# HVBoard.net
KiCad netlist of a schematic drawn in EAGLE
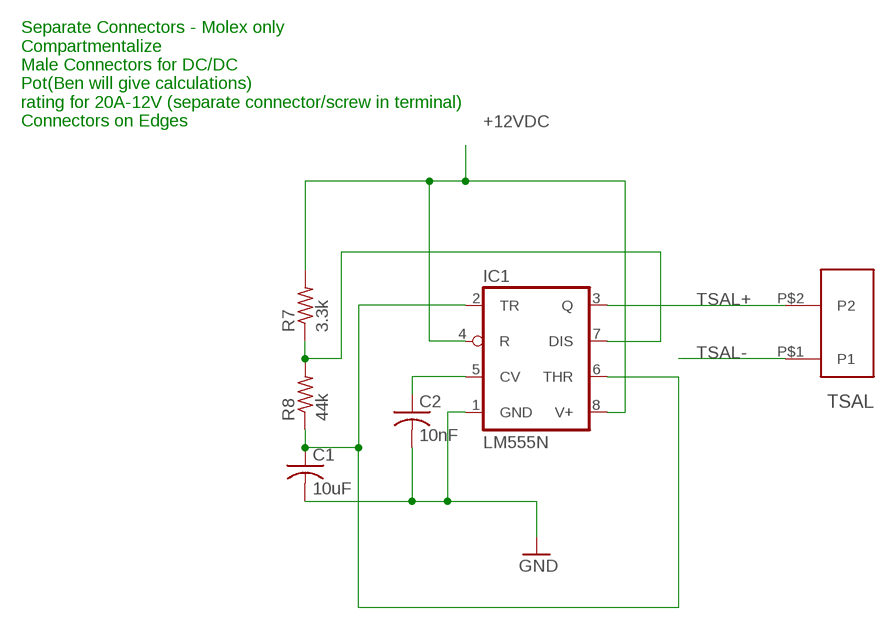
[diagram p0: schematic, sheet 1]
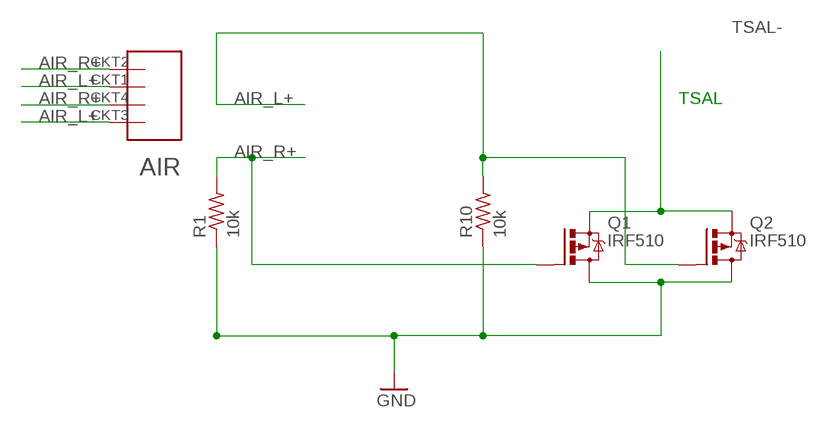
[diagram p1: schematic, sheet 2]
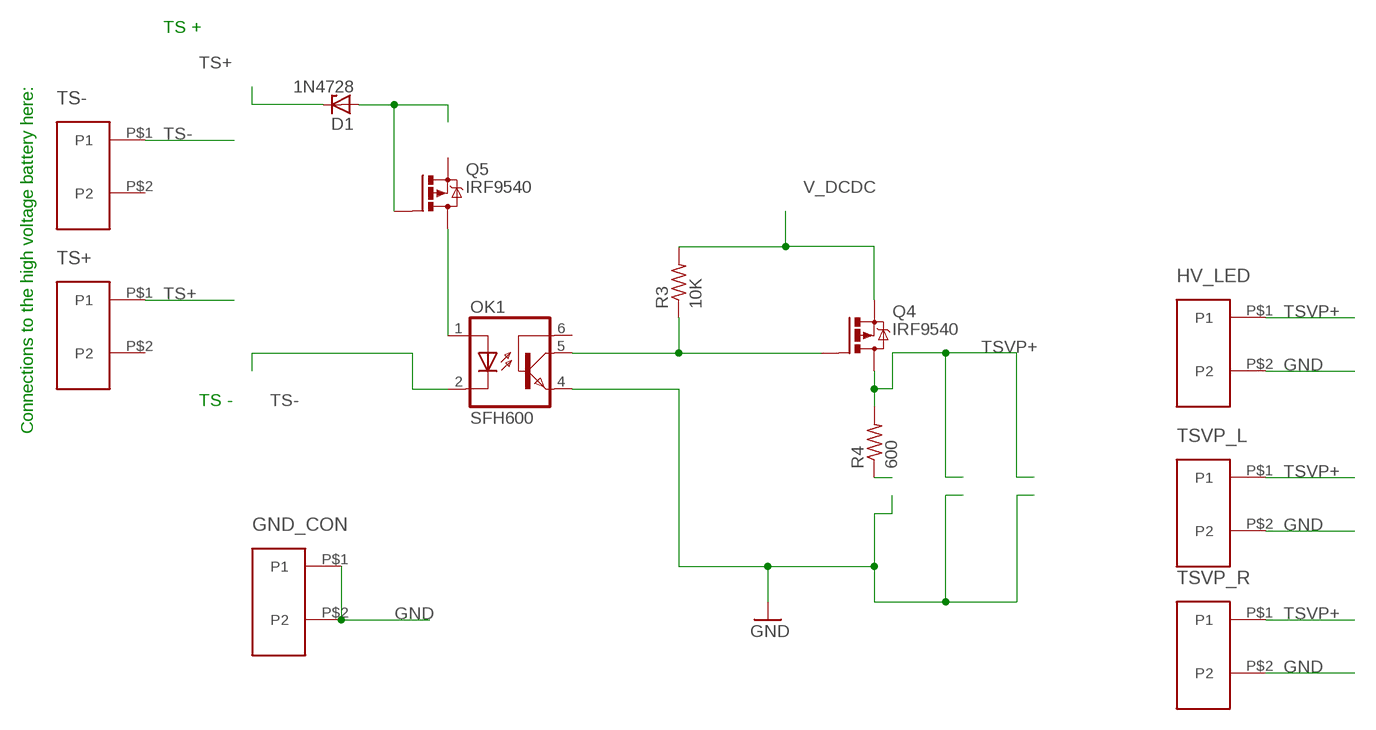
[diagram p2: schematic, sheet 3]
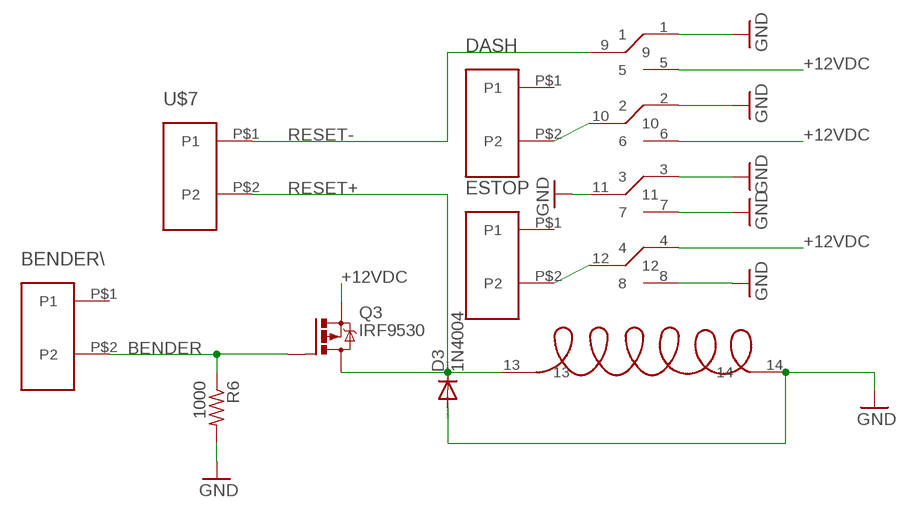
[diagram p3: schematic, sheet 4]
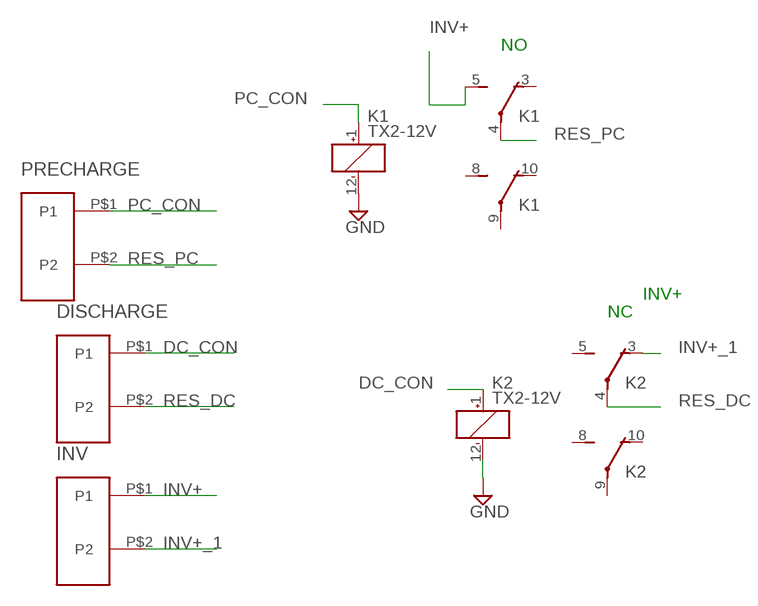
[diagram p4: schematic, sheet 5]
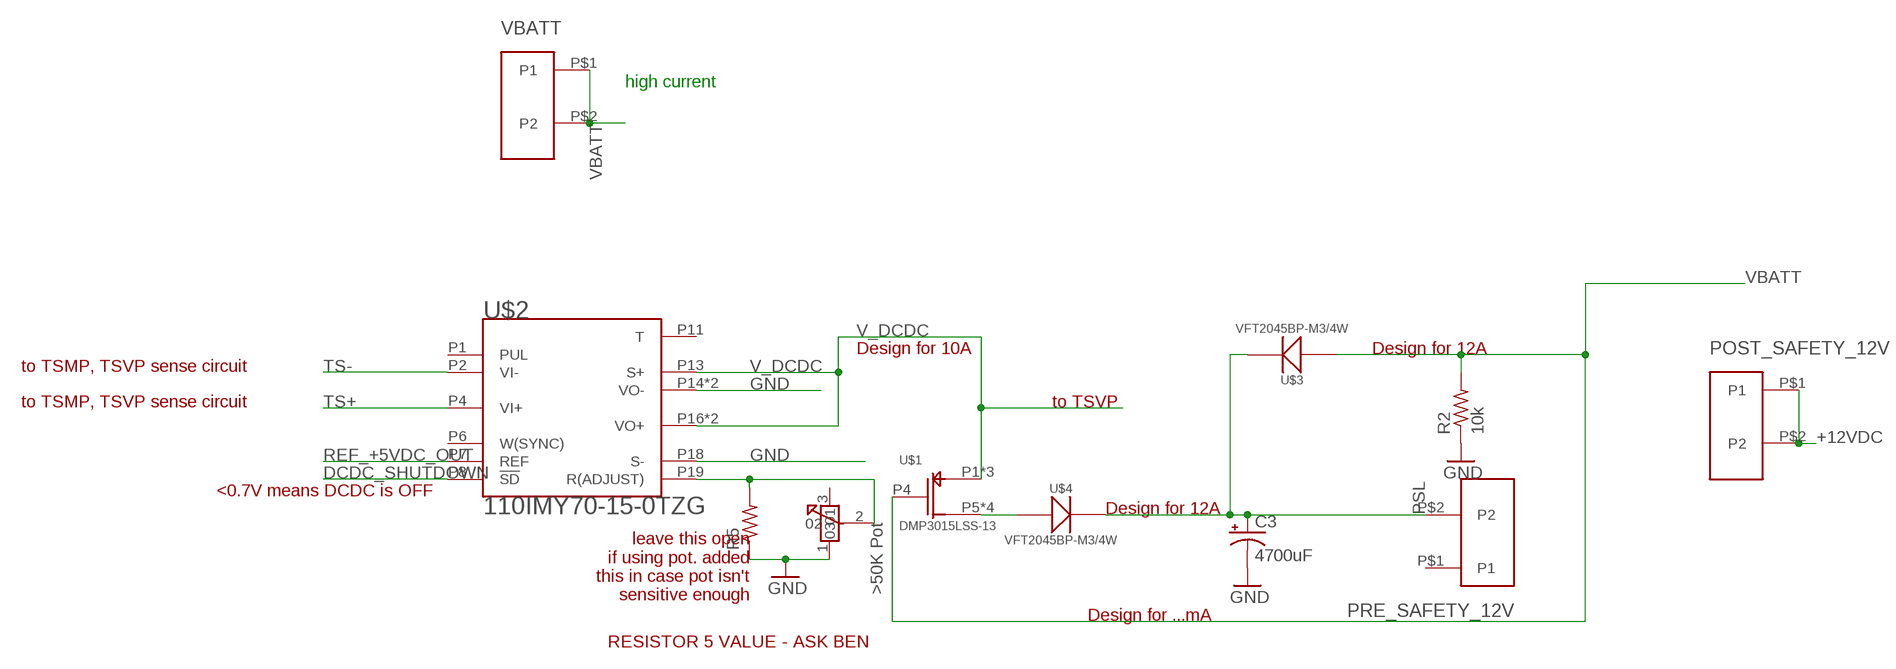
[diagram p5: schematic, sheet 6]

(export (version "E")
  (design (tool "Eeschema 10.0.6"))
  (components
    (comp (ref "DISCHARGE")
      (value "MINIFIT_2PIN")
      (footprint "eagle-import:2PIN_MOLEXMINIFIT")
      (libsource (lib "eagle-import") (part "MINIFIT_2PIN"))
    )
    (comp (ref "INV")
      (value "MINIFIT_2PIN")
      (footprint "eagle-import:2PIN_MOLEXMINIFIT")
      (libsource (lib "eagle-import") (part "MINIFIT_2PIN"))
    )
    (comp (ref "K1")
      (value "TX2-12V")
      (footprint "eagle-import:TX2")
      (fields (field (name "MF") "AROMAT/ MATSUSHITA"))
      (libsource (lib "eagle-import") (part "TX2?-12V"))
    )
    (comp (ref "K2")
      (value "TX2-12V")
      (footprint "eagle-import:TX2")
      (fields (field (name "MF") "AROMAT/ MATSUSHITA"))
      (libsource (lib "eagle-import") (part "TX2?-12V"))
    )
    (comp (ref "PRECHARGE")
      (value "MINIFIT_2PIN")
      (footprint "eagle-import:2PIN_MOLEXMINIFIT")
      (libsource (lib "eagle-import") (part "MINIFIT_2PIN"))
    )
    (comp (ref "AIR")
      (value "MHYBRIDMOLEX")
      (footprint "eagle-import:MOLEXMINIFIT6")
      (libsource (lib "eagle-import") (part "MHYBRIDMOLEX"))
    )
    (comp (ref "Q1")
      (value "IRF510")
      (footprint "eagle-import:TO220BV")
      (libsource (lib "eagle-import") (part "IRF9530"))
    )
    (comp (ref "Q2")
      (value "IRF510")
      (footprint "eagle-import:TO220BV")
      (libsource (lib "eagle-import") (part "IRF9530"))
    )
    (comp (ref "R1")
      (value "10k")
      (footprint "eagle-import:0207_7")
      (libsource (lib "eagle-import") (part "R-US_0207/7"))
    )
    (comp (ref "R10")
      (value "10k")
      (footprint "eagle-import:0207_7")
      (libsource (lib "eagle-import") (part "R-US_0207/7"))
    )
    (comp (ref "BENDER\\")
      (value "MINIFIT_2PIN")
      (footprint "eagle-import:2PIN_MOLEXMINIFIT")
      (libsource (lib "eagle-import") (part "MINIFIT_2PIN"))
    )
    (comp (ref "D3")
      (value "1N4004")
      (footprint "eagle-import:DO41-10")
      (libsource (lib "eagle-import") (part "1N4004"))
    )
    (comp (ref "DASH")
      (value "MINIFIT_2PIN")
      (footprint "eagle-import:2PIN_MOLEXMINIFIT")
      (libsource (lib "eagle-import") (part "MINIFIT_2PIN"))
    )
    (comp (ref "ESTOP")
      (value "MINIFIT_2PIN")
      (footprint "eagle-import:2PIN_MOLEXMINIFIT")
      (libsource (lib "eagle-import") (part "MINIFIT_2PIN"))
    )
    (comp (ref "NEW??1")
      (value "HJ4-DC12VHJ4-DC12V")
      (footprint "eagle-import:HJ4-DC12V")
      (libsource (lib "eagle-import") (part "HJ4-DC12VHJ4-DC12V"))
    )
    (comp (ref "Q3")
      (value "IRF9530")
      (footprint "eagle-import:TO220BV")
      (libsource (lib "eagle-import") (part "IRF9530"))
    )
    (comp (ref "R6")
      (value "1000")
      (footprint "eagle-import:M5923")
      (libsource (lib "eagle-import") (part "R-US_M5923"))
    )
    (comp (ref "U$7")
      (value "MINIFIT_2PIN")
      (footprint "eagle-import:2PIN_MOLEXMINIFIT")
      (libsource (lib "eagle-import") (part "MINIFIT_2PIN"))
    )
    (comp (ref "C1")
      (value "10uF")
      (footprint "eagle-import:C025-025X050")
      (libsource (lib "eagle-import") (part "C-US025-025X050"))
    )
    (comp (ref "C2")
      (value "10nF")
      (footprint "eagle-import:C025-025X050")
      (libsource (lib "eagle-import") (part "C-US025-025X050"))
    )
    (comp (ref "IC1")
      (value "LM555N")
      (footprint "eagle-import:DIL08")
      (libsource (lib "eagle-import") (part "555NLM"))
    )
    (comp (ref "R7")
      (value "3.3k")
      (footprint "eagle-import:0207_7")
      (libsource (lib "eagle-import") (part "R-US_0207/7"))
    )
    (comp (ref "R8")
      (value "44k")
      (footprint "eagle-import:0207_7")
      (libsource (lib "eagle-import") (part "R-US_0207/7"))
    )
    (comp (ref "TSAL")
      (value "MINIFIT_2PIN")
      (footprint "eagle-import:2PIN_MOLEXMINIFIT")
      (libsource (lib "eagle-import") (part "MINIFIT_2PIN"))
    )
    (comp (ref "D1")
      (value "1N4728")
      (footprint "eagle-import:DO41Z10")
      (libsource (lib "eagle-import") (part "1N4728"))
    )
    (comp (ref "GND_CON")
      (value "MINIFIT_2PIN")
      (footprint "eagle-import:2PIN_MOLEXMINIFIT")
      (libsource (lib "eagle-import") (part "MINIFIT_2PIN"))
    )
    (comp (ref "HV_LED")
      (value "MINIFIT_2PIN")
      (footprint "eagle-import:2PIN_MOLEXMINIFIT")
      (libsource (lib "eagle-import") (part "MINIFIT_2PIN"))
    )
    (comp (ref "OK1")
      (value "SFH600")
      (footprint "eagle-import:DIL06")
      (fields (field (name "MF") "VISHAY/TELEFUNKEN") (field (name "MPN") "SFH600-1"))
      (libsource (lib "eagle-import") (part "SFH600"))
    )
    (comp (ref "Q4")
      (value "IRF9540")
      (footprint "eagle-import:TO220BV")
      (libsource (lib "eagle-import") (part "IRF9530"))
    )
    (comp (ref "Q5")
      (value "IRF9540")
      (footprint "eagle-import:TO220BV")
      (libsource (lib "eagle-import") (part "IRF9530"))
    )
    (comp (ref "R3")
      (value "10K")
      (footprint "eagle-import:R0603")
      (libsource (lib "eagle-import") (part "resistor_R-US_R0603"))
    )
    (comp (ref "R4")
      (value "600")
      (footprint "eagle-import:R0603")
      (libsource (lib "eagle-import") (part "resistor_R-US_R0603"))
    )
    (comp (ref "TS+")
      (value "MINIFIT_2PIN")
      (footprint "eagle-import:2PIN_MOLEXMINIFIT")
      (libsource (lib "eagle-import") (part "MINIFIT_2PIN"))
    )
    (comp (ref "TS-")
      (value "MINIFIT_2PIN")
      (footprint "eagle-import:2PIN_MOLEXMINIFIT")
      (libsource (lib "eagle-import") (part "MINIFIT_2PIN"))
    )
    (comp (ref "TSVP_L")
      (value "MINIFIT_2PIN")
      (footprint "eagle-import:2PIN_MOLEXMINIFIT")
      (libsource (lib "eagle-import") (part "MINIFIT_2PIN"))
    )
    (comp (ref "TSVP_R")
      (value "MINIFIT_2PIN")
      (footprint "eagle-import:2PIN_MOLEXMINIFIT")
      (libsource (lib "eagle-import") (part "MINIFIT_2PIN"))
    )
    (comp (ref "C3")
      (value "4700uF")
      (footprint "eagle-import:CPOL-RADIAL-1000UF-63V")
      (libsource (lib "eagle-import") (part "CAP_POLPTH3"))
    )
    (comp (ref "POST_SAFETY_12V")
      (value "MINIFIT_2PIN")
      (footprint "eagle-import:2PIN_MOLEXMINIFIT")
      (libsource (lib "eagle-import") (part "MINIFIT_2PIN"))
    )
    (comp (ref "POT1")
      (value "3310P-001-503L-NP")
      (footprint "eagle-import:3310P-001-503L-NP")
      (libsource (lib "eagle-import") (part "3310P-001-503L-NP"))
    )
    (comp (ref "PRE_SAFETY_12V")
      (value "MINIFIT_2PIN")
      (footprint "eagle-import:2PIN_MOLEXMINIFIT")
      (libsource (lib "eagle-import") (part "MINIFIT_2PIN"))
    )
    (comp (ref "R2")
      (value "10k")
      (footprint "eagle-import:R0603")
      (libsource (lib "eagle-import") (part "resistor_R-US_R0603"))
    )
    (comp (ref "R5")
      (value "R-US_R0805")
      (footprint "eagle-import:R0805")
      (libsource (lib "eagle-import") (part "R-US_R0805"))
    )
    (comp (ref "U$1")
      (value "DMP3015LSS-13")
      (footprint "eagle-import:8-SOP")
      (fields (field (name "MANUFACTURER") "Diodes Incorporated"))
      (libsource (lib "eagle-import") (part "DMP3015LSS-13"))
    )
    (comp (ref "U$2")
      (value "110IMY70-15-0TZG")
      (footprint "eagle-import:110IMY70-15-0TZG")
      (libsource (lib "eagle-import") (part "110IMY70-15-0TZG"))
    )
    (comp (ref "U$3")
      (value "VFT2045BP-M3/4W")
      (footprint "eagle-import:VFT2045BP-M3_4W")
      (fields (field (name "MANUFACTURER") "Vishay Semiconductor Diodes Division"))
      (libsource (lib "eagle-import") (part "VFT2045BP-M3/4W"))
    )
    (comp (ref "U$4")
      (value "VFT2045BP-M3/4W")
      (footprint "eagle-import:VFT2045BP-M3_4W")
      (fields (field (name "MANUFACTURER") "Vishay Semiconductor Diodes Division"))
      (libsource (lib "eagle-import") (part "VFT2045BP-M3/4W"))
    )
    (comp (ref "VBATT")
      (value "MINIFIT_2PIN")
      (footprint "eagle-import:2PIN_MOLEXMINIFIT")
      (libsource (lib "eagle-import") (part "MINIFIT_2PIN"))
    )
  )
  (nets
    (net (code "1") (name "+12VDC") (class "Default")
      (node (ref "IC1") (pin "4") (pinfunction "R_4") (pintype "input"))
      (node (ref "IC1") (pin "8") (pinfunction "V+_8") (pintype "power_in"))
      (node (ref "NEW??1") (pin "4") (pinfunction "4_4") (pintype "bidirectional"))
      (node (ref "NEW??1") (pin "5") (pinfunction "5_5") (pintype "bidirectional"))
      (node (ref "NEW??1") (pin "6") (pinfunction "6_6") (pintype "bidirectional"))
      (node (ref "POST_SAFETY_12V") (pin "P$1") (pinfunction "P1_P$1") (pintype "bidirectional"))
      (node (ref "POST_SAFETY_12V") (pin "P$2") (pinfunction "P2_P$2") (pintype "bidirectional"))
      (node (ref "Q3") (pin "S") (pinfunction "S_S") (pintype "passive"))
      (node (ref "R7") (pin "2") (pinfunction "2_2") (pintype "passive"))
    )
    (net (code "2") (name "AIR_L+") (class "Default")
      (node (ref "AIR") (pin "CKT1") (pinfunction "GND_CKT1") (pintype "bidirectional"))
      (node (ref "AIR") (pin "CKT3") (pinfunction "V_IN(12)_CKT3") (pintype "bidirectional"))
      (node (ref "Q2") (pin "G") (pinfunction "G_G") (pintype "passive"))
      (node (ref "R10") (pin "2") (pinfunction "2_2") (pintype "passive"))
    )
    (net (code "3") (name "AIR_R+") (class "Default")
      (node (ref "AIR") (pin "CKT2") (pinfunction "GND2_CKT2") (pintype "bidirectional"))
      (node (ref "AIR") (pin "CKT4") (pinfunction "V_IN2(12)_CKT4") (pintype "bidirectional"))
      (node (ref "Q1") (pin "G") (pinfunction "G_G") (pintype "passive"))
      (node (ref "R1") (pin "2") (pinfunction "2_2") (pintype "passive"))
    )
    (net (code "4") (name "BENDER") (class "Default")
      (node (ref "BENDER\\") (pin "P$2") (pinfunction "P2_P$2") (pintype "bidirectional"))
      (node (ref "Q3") (pin "G") (pinfunction "G_G") (pintype "passive"))
      (node (ref "R6") (pin "1") (pinfunction "1_1") (pintype "passive"))
    )
    (net (code "5") (name "DCDC_SHUTDOWN") (class "Default")
      (node (ref "U$2") (pin "P8") (pinfunction "~{SD}_P8") (pintype "bidirectional"))
    )
    (net (code "6") (name "DC_CON") (class "Default")
      (node (ref "DISCHARGE") (pin "P$1") (pinfunction "P1_P$1") (pintype "bidirectional"))
      (node (ref "K2") (pin "1") (pinfunction "+_1") (pintype "passive"))
    )
    (net (code "7") (name "GND") (class "Default")
      (node (ref "C1") (pin "2") (pinfunction "2_2") (pintype "passive"))
      (node (ref "C2") (pin "2") (pinfunction "2_2") (pintype "passive"))
      (node (ref "C3") (pin "2") (pinfunction "-_2") (pintype "passive"))
      (node (ref "D3") (pin "A") (pinfunction "A_A") (pintype "passive"))
      (node (ref "GND_CON") (pin "P$1") (pinfunction "P1_P$1") (pintype "bidirectional"))
      (node (ref "GND_CON") (pin "P$2") (pinfunction "P2_P$2") (pintype "bidirectional"))
      (node (ref "HV_LED") (pin "P$2") (pinfunction "P2_P$2") (pintype "bidirectional"))
      (node (ref "IC1") (pin "1") (pinfunction "GND_1") (pintype "power_in"))
      (node (ref "K1") (pin "12") (pinfunction "-_12") (pintype "passive"))
      (node (ref "K2") (pin "12") (pinfunction "-_12") (pintype "passive"))
      (node (ref "NEW??1") (pin "1") (pinfunction "1_1") (pintype "bidirectional"))
      (node (ref "NEW??1") (pin "11") (pinfunction "11_11") (pintype "bidirectional"))
      (node (ref "NEW??1") (pin "14") (pinfunction "14_14") (pintype "bidirectional"))
      (node (ref "NEW??1") (pin "2") (pinfunction "2_2") (pintype "bidirectional"))
      (node (ref "NEW??1") (pin "3") (pinfunction "3_3") (pintype "bidirectional"))
      (node (ref "NEW??1") (pin "7") (pinfunction "7_7") (pintype "bidirectional"))
      (node (ref "NEW??1") (pin "8") (pinfunction "8_8") (pintype "bidirectional"))
      (node (ref "OK1") (pin "4") (pinfunction "EMI_4") (pintype "passive"))
      (node (ref "POT1") (pin "1") (pinfunction "01_1") (pintype "bidirectional"))
      (node (ref "Q1") (pin "D") (pinfunction "D_D") (pintype "passive"))
      (node (ref "Q2") (pin "D") (pinfunction "D_D") (pintype "passive"))
      (node (ref "R1") (pin "1") (pinfunction "1_1") (pintype "passive"))
      (node (ref "R10") (pin "1") (pinfunction "1_1") (pintype "passive"))
      (node (ref "R2") (pin "1") (pinfunction "1_1") (pintype "passive"))
      (node (ref "R5") (pin "1") (pinfunction "1_1") (pintype "passive"))
      (node (ref "R6") (pin "2") (pinfunction "2_2") (pintype "passive"))
      (node (ref "TSVP_L") (pin "P$2") (pinfunction "P2_P$2") (pintype "bidirectional"))
      (node (ref "TSVP_R") (pin "P$2") (pinfunction "P2_P$2") (pintype "bidirectional"))
      (node (ref "U$2") (pin "P14") (pinfunction "VO-_P14") (pintype "bidirectional"))
      (node (ref "U$2") (pin "P15") (pinfunction "VO-_P15") (pintype "bidirectional"))
      (node (ref "U$2") (pin "P18") (pinfunction "S-_P18") (pintype "bidirectional"))
    )
    (net (code "8") (name "INV+") (class "Default")
      (node (ref "INV") (pin "P$1") (pinfunction "P1_P$1") (pintype "bidirectional"))
      (node (ref "K1") (pin "5") (pinfunction "S_5") (pintype "passive"))
    )
    (net (code "9") (name "INV+_1") (class "Default")
      (node (ref "INV") (pin "P$2") (pinfunction "P2_P$2") (pintype "bidirectional"))
      (node (ref "K2") (pin "3") (pinfunction "O_3") (pintype "passive"))
    )
    (net (code "10") (name "Net-(D1-PadA)") (class "Default")
      (node (ref "D1") (pin "A") (pinfunction "A_A") (pintype "passive"))
      (node (ref "Q5") (pin "G") (pinfunction "G_G") (pintype "passive"))
    )
    (net (code "11") (name "Net-(DASH-P2)") (class "Default")
      (node (ref "DASH") (pin "P$2") (pinfunction "P2_P$2") (pintype "bidirectional"))
      (node (ref "NEW??1") (pin "10") (pinfunction "10_10") (pintype "bidirectional"))
    )
    (net (code "12") (name "Net-(ESTOP-P2)") (class "Default")
      (node (ref "ESTOP") (pin "P$2") (pinfunction "P2_P$2") (pintype "bidirectional"))
      (node (ref "NEW??1") (pin "12") (pinfunction "12_12") (pintype "bidirectional"))
    )
    (net (code "13") (name "Net-(IC1-CV)") (class "Default")
      (node (ref "C2") (pin "1") (pinfunction "1_1") (pintype "passive"))
      (node (ref "IC1") (pin "5") (pinfunction "CV_5") (pintype "input"))
    )
    (net (code "14") (name "Net-(IC1-DIS)") (class "Default")
      (node (ref "IC1") (pin "7") (pinfunction "DIS_7") (pintype "input"))
      (node (ref "R7") (pin "1") (pinfunction "1_1") (pintype "passive"))
      (node (ref "R8") (pin "2") (pinfunction "2_2") (pintype "passive"))
    )
    (net (code "15") (name "Net-(IC1-THR)") (class "Default")
      (node (ref "C1") (pin "1") (pinfunction "1_1") (pintype "passive"))
      (node (ref "IC1") (pin "2") (pinfunction "TR_2") (pintype "input"))
      (node (ref "IC1") (pin "6") (pinfunction "THR_6") (pintype "input"))
      (node (ref "R8") (pin "1") (pinfunction "1_1") (pintype "passive"))
    )
    (net (code "16") (name "Net-(OK1-A)") (class "Default")
      (node (ref "OK1") (pin "1") (pinfunction "A_1") (pintype "passive"))
      (node (ref "Q5") (pin "D") (pinfunction "D_D") (pintype "passive"))
    )
    (net (code "17") (name "Net-(OK1-COL)") (class "Default")
      (node (ref "OK1") (pin "5") (pinfunction "COL_5") (pintype "passive"))
      (node (ref "Q4") (pin "G") (pinfunction "G_G") (pintype "passive"))
      (node (ref "R3") (pin "1") (pinfunction "1_1") (pintype "passive"))
    )
    (net (code "18") (name "Net-(POT1-02)") (class "Default")
      (node (ref "POT1") (pin "2") (pinfunction "02_2") (pintype "bidirectional"))
      (node (ref "R5") (pin "2") (pinfunction "2_2") (pintype "passive"))
      (node (ref "U$2") (pin "P19") (pinfunction "R(ADJUST)_P19") (pintype "bidirectional"))
    )
    (net (code "19") (name "Net-(U$1-D-PadP5)") (class "Default")
      (node (ref "U$1") (pin "P5") (pinfunction "D_P5") (pintype "bidirectional"))
      (node (ref "U$1") (pin "P6") (pinfunction "D_P6") (pintype "bidirectional"))
      (node (ref "U$1") (pin "P7") (pinfunction "D_P7") (pintype "bidirectional"))
      (node (ref "U$1") (pin "P8") (pinfunction "D_P8") (pintype "bidirectional"))
      (node (ref "U$4") (pin "P1") (pinfunction "P1_P1") (pintype "bidirectional"))
    )
    (net (code "20") (name "PC_CON") (class "Default")
      (node (ref "K1") (pin "1") (pinfunction "+_1") (pintype "passive"))
      (node (ref "PRECHARGE") (pin "P$1") (pinfunction "P1_P$1") (pintype "bidirectional"))
    )
    (net (code "21") (name "PSL") (class "Default")
      (node (ref "C3") (pin "1") (pinfunction "+_1") (pintype "passive"))
      (node (ref "PRE_SAFETY_12V") (pin "P$2") (pinfunction "P2_P$2") (pintype "bidirectional"))
      (node (ref "U$3") (pin "P2") (pinfunction "P2_P2") (pintype "bidirectional"))
      (node (ref "U$4") (pin "P2") (pinfunction "P2_P2") (pintype "bidirectional"))
    )
    (net (code "22") (name "REF_+5VDC_OUT") (class "Default")
      (node (ref "U$2") (pin "P7") (pinfunction "REF_P7") (pintype "bidirectional"))
    )
    (net (code "23") (name "RESET+") (class "Default")
      (node (ref "D3") (pin "C") (pinfunction "C_C") (pintype "passive"))
      (node (ref "NEW??1") (pin "13") (pinfunction "13_13") (pintype "bidirectional"))
      (node (ref "Q3") (pin "D") (pinfunction "D_D") (pintype "passive"))
      (node (ref "U$7") (pin "P$2") (pinfunction "P2_P$2") (pintype "bidirectional"))
    )
    (net (code "24") (name "RESET-") (class "Default")
      (node (ref "NEW??1") (pin "9") (pinfunction "9_9") (pintype "bidirectional"))
      (node (ref "U$7") (pin "P$1") (pinfunction "P1_P$1") (pintype "bidirectional"))
    )
    (net (code "25") (name "RES_DC") (class "Default")
      (node (ref "DISCHARGE") (pin "P$2") (pinfunction "P2_P$2") (pintype "bidirectional"))
      (node (ref "K2") (pin "4") (pinfunction "P_4") (pintype "passive"))
    )
    (net (code "26") (name "RES_PC") (class "Default")
      (node (ref "K1") (pin "4") (pinfunction "P_4") (pintype "passive"))
      (node (ref "PRECHARGE") (pin "P$2") (pinfunction "P2_P$2") (pintype "bidirectional"))
    )
    (net (code "27") (name "TS+") (class "Default")
      (node (ref "D1") (pin "C") (pinfunction "C_C") (pintype "passive"))
      (node (ref "TS+") (pin "P$1") (pinfunction "P1_P$1") (pintype "bidirectional"))
      (node (ref "U$2") (pin "P4") (pinfunction "VI+_P4") (pintype "bidirectional"))
    )
    (net (code "28") (name "TS-") (class "Default")
      (node (ref "OK1") (pin "2") (pinfunction "C_2") (pintype "passive"))
      (node (ref "TS-") (pin "P$1") (pinfunction "P1_P$1") (pintype "bidirectional"))
      (node (ref "U$2") (pin "P2") (pinfunction "VI-_P2") (pintype "bidirectional"))
    )
    (net (code "29") (name "TSAL+") (class "Default")
      (node (ref "IC1") (pin "3") (pinfunction "Q_3") (pintype "output"))
      (node (ref "TSAL") (pin "P$2") (pinfunction "P2_P$2") (pintype "bidirectional"))
    )
    (net (code "30") (name "TSAL-") (class "Default")
      (node (ref "Q1") (pin "S") (pinfunction "S_S") (pintype "passive"))
      (node (ref "Q2") (pin "S") (pinfunction "S_S") (pintype "passive"))
      (node (ref "TSAL") (pin "P$1") (pinfunction "P1_P$1") (pintype "bidirectional"))
    )
    (net (code "31") (name "TSVP+") (class "Default")
      (node (ref "HV_LED") (pin "P$1") (pinfunction "P1_P$1") (pintype "bidirectional"))
      (node (ref "Q4") (pin "D") (pinfunction "D_D") (pintype "passive"))
      (node (ref "R4") (pin "2") (pinfunction "2_2") (pintype "passive"))
      (node (ref "TSVP_L") (pin "P$1") (pinfunction "P1_P$1") (pintype "bidirectional"))
      (node (ref "TSVP_R") (pin "P$1") (pinfunction "P1_P$1") (pintype "bidirectional"))
    )
    (net (code "32") (name "VBATT") (class "Default")
      (node (ref "R2") (pin "2") (pinfunction "2_2") (pintype "passive"))
      (node (ref "U$1") (pin "P4") (pinfunction "G_P4") (pintype "bidirectional"))
      (node (ref "U$3") (pin "P1") (pinfunction "P1_P1") (pintype "bidirectional"))
      (node (ref "VBATT") (pin "P$1") (pinfunction "P1_P$1") (pintype "bidirectional"))
      (node (ref "VBATT") (pin "P$2") (pinfunction "P2_P$2") (pintype "bidirectional"))
    )
    (net (code "33") (name "V_DCDC") (class "Default")
      (node (ref "Q4") (pin "S") (pinfunction "S_S") (pintype "passive"))
      (node (ref "R3") (pin "2") (pinfunction "2_2") (pintype "passive"))
      (node (ref "U$1") (pin "P1") (pinfunction "S_P1") (pintype "bidirectional"))
      (node (ref "U$1") (pin "P2") (pinfunction "S_P2") (pintype "bidirectional"))
      (node (ref "U$1") (pin "P3") (pinfunction "S_P3") (pintype "bidirectional"))
      (node (ref "U$2") (pin "P13") (pinfunction "S+_P13") (pintype "bidirectional"))
      (node (ref "U$2") (pin "P16") (pinfunction "VO+_P16") (pintype "bidirectional"))
      (node (ref "U$2") (pin "P17") (pinfunction "VO+_P17") (pintype "bidirectional"))
    )
    (net (code "34") (name "unconnected-(BENDER\\-P1-PadP$1)") (class "Default")
      (node (ref "BENDER\\") (pin "P$1") (pinfunction "P1_P$1") (pintype "bidirectional"))
    )
    (net (code "35") (name "unconnected-(DASH-P1-PadP$1)") (class "Default")
      (node (ref "DASH") (pin "P$1") (pinfunction "P1_P$1") (pintype "bidirectional"))
    )
    (net (code "36") (name "unconnected-(ESTOP-P1-PadP$1)") (class "Default")
      (node (ref "ESTOP") (pin "P$1") (pinfunction "P1_P$1") (pintype "bidirectional"))
    )
    (net (code "37") (name "unconnected-(K1A-O-Pad3)") (class "Default")
      (node (ref "K1") (pin "3") (pinfunction "O_3") (pintype "passive"))
    )
    (net (code "38") (name "unconnected-(K1B-O-Pad10)") (class "Default")
      (node (ref "K1") (pin "10") (pinfunction "O_10") (pintype "passive"))
    )
    (net (code "39") (name "unconnected-(K1B-P-Pad9)") (class "Default")
      (node (ref "K1") (pin "9") (pinfunction "P_9") (pintype "passive"))
    )
    (net (code "40") (name "unconnected-(K1B-S-Pad8)") (class "Default")
      (node (ref "K1") (pin "8") (pinfunction "S_8") (pintype "passive"))
    )
    (net (code "41") (name "unconnected-(K2A-S-Pad5)") (class "Default")
      (node (ref "K2") (pin "5") (pinfunction "S_5") (pintype "passive"))
    )
    (net (code "42") (name "unconnected-(K2B-O-Pad10)") (class "Default")
      (node (ref "K2") (pin "10") (pinfunction "O_10") (pintype "passive"))
    )
    (net (code "43") (name "unconnected-(K2B-P-Pad9)") (class "Default")
      (node (ref "K2") (pin "9") (pinfunction "P_9") (pintype "passive"))
    )
    (net (code "44") (name "unconnected-(K2B-S-Pad8)") (class "Default")
      (node (ref "K2") (pin "8") (pinfunction "S_8") (pintype "passive"))
    )
    (net (code "45") (name "unconnected-(OK1-BAS-Pad6)") (class "Default")
      (node (ref "OK1") (pin "6") (pinfunction "BAS_6") (pintype "passive"))
    )
    (net (code "46") (name "unconnected-(POT1-03-Pad3)") (class "Default")
      (node (ref "POT1") (pin "3") (pinfunction "03_3") (pintype "bidirectional"))
    )
    (net (code "47") (name "unconnected-(PRE_SAFETY_12V-P1-PadP$1)") (class "Default")
      (node (ref "PRE_SAFETY_12V") (pin "P$1") (pinfunction "P1_P$1") (pintype "bidirectional"))
    )
    (net (code "48") (name "unconnected-(Q5-PadS)") (class "Default")
      (node (ref "Q5") (pin "S") (pinfunction "S_S") (pintype "passive"))
    )
    (net (code "49") (name "unconnected-(R4-Pad1)") (class "Default")
      (node (ref "R4") (pin "1") (pinfunction "1_1") (pintype "passive"))
    )
    (net (code "50") (name "unconnected-(TS+-P2-PadP$2)") (class "Default")
      (node (ref "TS+") (pin "P$2") (pinfunction "P2_P$2") (pintype "bidirectional"))
    )
    (net (code "51") (name "unconnected-(TS--P2-PadP$2)") (class "Default")
      (node (ref "TS-") (pin "P$2") (pinfunction "P2_P$2") (pintype "bidirectional"))
    )
    (net (code "52") (name "unconnected-(U$2-PUL-PadP1)") (class "Default")
      (node (ref "U$2") (pin "P1") (pinfunction "PUL_P1") (pintype "bidirectional"))
    )
    (net (code "53") (name "unconnected-(U$2-T-PadP11)") (class "Default")
      (node (ref "U$2") (pin "P11") (pinfunction "T_P11") (pintype "bidirectional"))
    )
    (net (code "54") (name "unconnected-(U$2-W(SYNC)-PadP6)") (class "Default")
      (node (ref "U$2") (pin "P6") (pinfunction "W(SYNC)_P6") (pintype "bidirectional"))
    )
  )
)
